# 9_-_STM32F407_Controller.net
KiCad netlist of a schematic drawn in Altium Designer
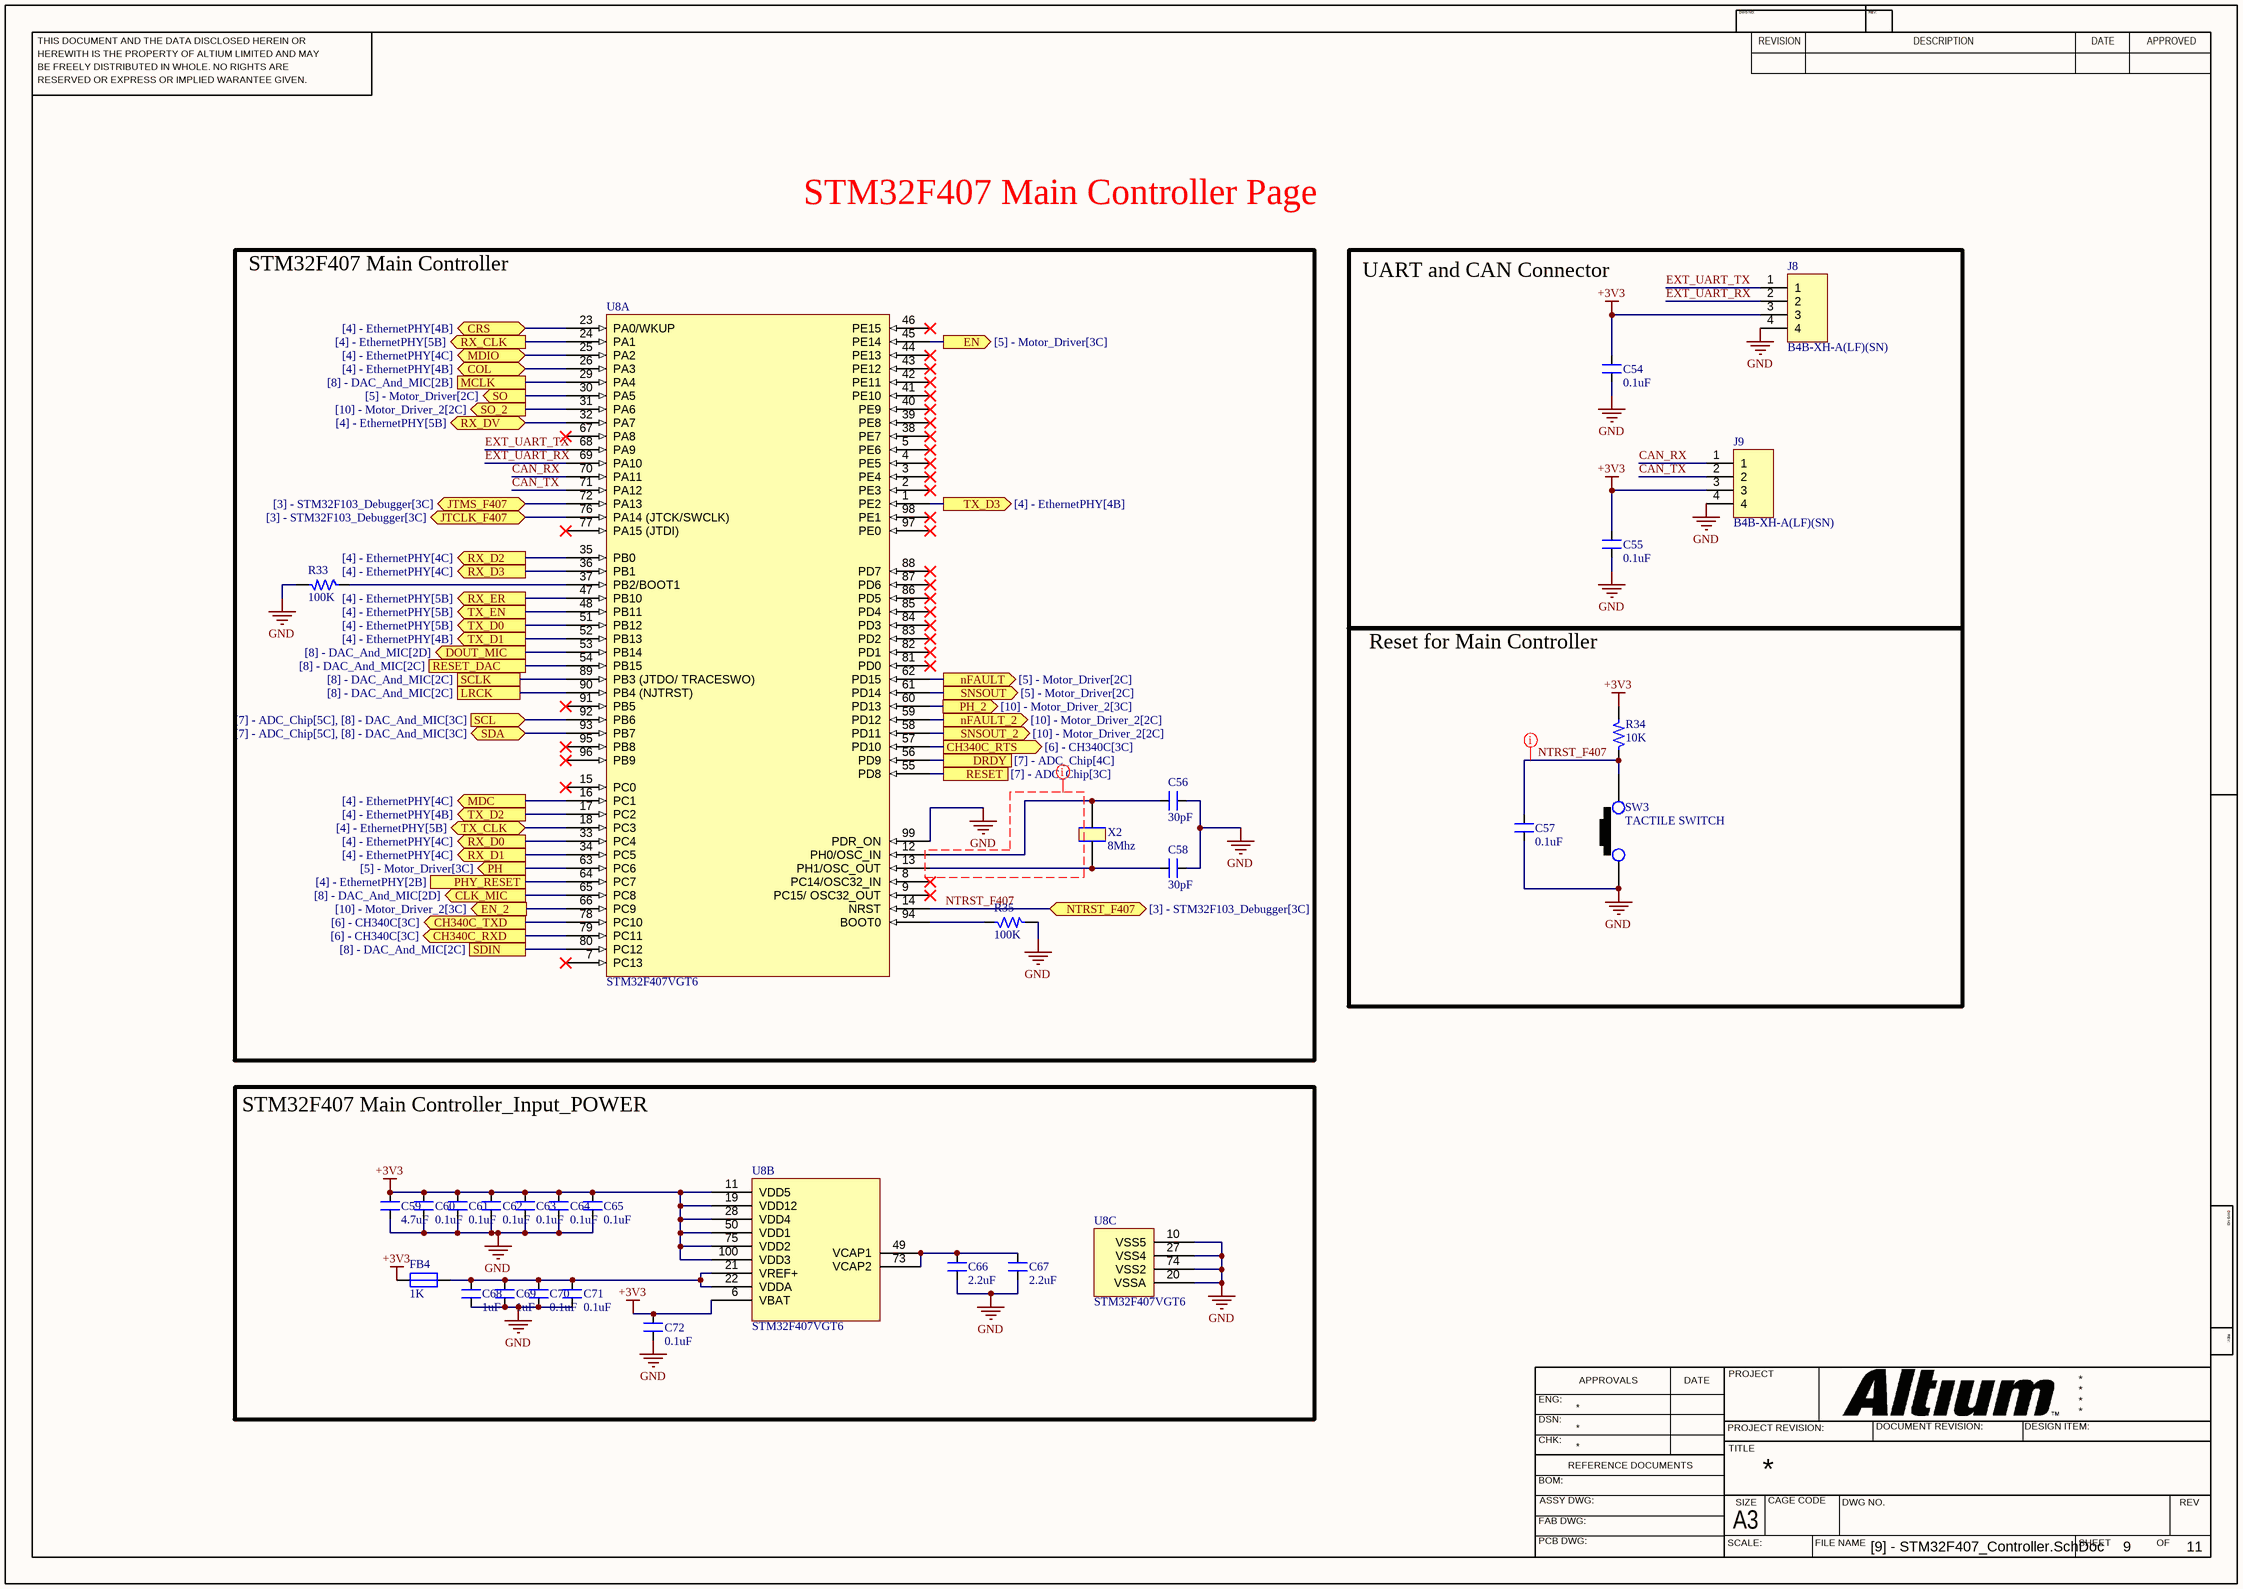
[diagram p0: [9] - STM32F407_Controller.SchDoc]

(export (version "E")
  (design (tool "Eeschema 10.0.6"))
  (components
    (comp (ref "C54")
      (value "0.1uF")
      (footprint "CAP_0805")
      (description "0.1µF ±5% 50V Ceramic Capacitor X7R 0805 (2012 Metric)")
      (fields
        (field (name "MANUFACTURER") "AVX Corporation")
        (field (name "MANUFACTURER PART NUMBER") "08055C104JAT4A")
      )
      (libsource (lib "ESTEEMPCBLIB") (part "CAP_0.1uF-50V-5%-0805"))
    )
    (comp (ref "C55")
      (value "0.1uF")
      (footprint "CAP_0805")
      (description "0.1µF ±5% 50V Ceramic Capacitor X7R 0805 (2012 Metric)")
      (fields
        (field (name "MANUFACTURER") "AVX Corporation")
        (field (name "MANUFACTURER PART NUMBER") "08055C104JAT4A")
      )
      (libsource (lib "ESTEEMPCBLIB") (part "CAP_0.1uF-50V-5%-0805"))
    )
    (comp (ref "C56")
      (value "30pF")
      (footprint "CAP_0805")
      (description "±10% 50V Ceramic Capacitor C0G, NP0 0805 (2012 Metric)")
      (fields
        (field (name "MANUFACTURER PART NUMBER") "C0805C300K5GAC7800")
        (field (name "MANUFACTURER") "KEMET")
      )
      (libsource (lib "ESTEEMPCBLIB") (part "CAP_30pF-50V-10%-0805"))
    )
    (comp (ref "C57")
      (value "0.1uF")
      (footprint "CAP_0805")
      (description "0.1µF ±5% 50V Ceramic Capacitor X7R 0805 (2012 Metric)")
      (fields
        (field (name "MANUFACTURER") "AVX Corporation")
        (field (name "MANUFACTURER PART NUMBER") "08055C104JAT4A")
      )
      (libsource (lib "ESTEEMPCBLIB") (part "CAP_0.1uF-50V-5%-0805"))
    )
    (comp (ref "C58")
      (value "30pF")
      (footprint "CAP_0805")
      (description "±10% 50V Ceramic Capacitor C0G, NP0 0805 (2012 Metric)")
      (fields
        (field (name "MANUFACTURER PART NUMBER") "C0805C300K5GAC7800")
        (field (name "MANUFACTURER") "KEMET")
      )
      (libsource (lib "ESTEEMPCBLIB") (part "CAP_30pF-50V-10%-0805"))
    )
    (comp (ref "C59")
      (value "4.7uF")
      (footprint "CAP_0805")
      (description "4.7µF ±10% 50V Ceramic Capacitor X5R 0805 (2012 Metric)")
      (fields
        (field (name "MANUFACTURER") "Yageo")
        (field (name "MANUFACTURER PART NUMBER") "GRM21BR61H475KE51L")
      )
      (libsource (lib "ESTEEMPCBLIB") (part "CAP_4.7uF-50V-10%-0805"))
    )
    (comp (ref "C60")
      (value "0.1uF")
      (footprint "CAP_0805")
      (description "0.1µF ±5% 50V Ceramic Capacitor X7R 0805 (2012 Metric)")
      (fields
        (field (name "MANUFACTURER") "AVX Corporation")
        (field (name "MANUFACTURER PART NUMBER") "08055C104JAT4A")
      )
      (libsource (lib "ESTEEMPCBLIB") (part "CAP_0.1uF-50V-5%-0805"))
    )
    (comp (ref "C61")
      (value "0.1uF")
      (footprint "CAP_0805")
      (description "0.1µF ±5% 50V Ceramic Capacitor X7R 0805 (2012 Metric)")
      (fields
        (field (name "MANUFACTURER") "AVX Corporation")
        (field (name "MANUFACTURER PART NUMBER") "08055C104JAT4A")
      )
      (libsource (lib "ESTEEMPCBLIB") (part "CAP_0.1uF-50V-5%-0805"))
    )
    (comp (ref "C62")
      (value "0.1uF")
      (footprint "CAP_0805")
      (description "0.1µF ±5% 50V Ceramic Capacitor X7R 0805 (2012 Metric)")
      (fields
        (field (name "MANUFACTURER") "AVX Corporation")
        (field (name "MANUFACTURER PART NUMBER") "08055C104JAT4A")
      )
      (libsource (lib "ESTEEMPCBLIB") (part "CAP_0.1uF-50V-5%-0805"))
    )
    (comp (ref "C63")
      (value "0.1uF")
      (footprint "CAP_0805")
      (description "0.1µF ±5% 50V Ceramic Capacitor X7R 0805 (2012 Metric)")
      (fields
        (field (name "MANUFACTURER") "AVX Corporation")
        (field (name "MANUFACTURER PART NUMBER") "08055C104JAT4A")
      )
      (libsource (lib "ESTEEMPCBLIB") (part "CAP_0.1uF-50V-5%-0805"))
    )
    (comp (ref "C64")
      (value "0.1uF")
      (footprint "CAP_0805")
      (description "0.1µF ±5% 50V Ceramic Capacitor X7R 0805 (2012 Metric)")
      (fields
        (field (name "MANUFACTURER") "AVX Corporation")
        (field (name "MANUFACTURER PART NUMBER") "08055C104JAT4A")
      )
      (libsource (lib "ESTEEMPCBLIB") (part "CAP_0.1uF-50V-5%-0805"))
    )
    (comp (ref "C65")
      (value "0.1uF")
      (footprint "CAP_0805")
      (description "0.1µF ±5% 50V Ceramic Capacitor X7R 0805 (2012 Metric)")
      (fields
        (field (name "MANUFACTURER") "AVX Corporation")
        (field (name "MANUFACTURER PART NUMBER") "08055C104JAT4A")
      )
      (libsource (lib "ESTEEMPCBLIB") (part "CAP_0.1uF-50V-5%-0805"))
    )
    (comp (ref "C66")
      (value "2.2uF")
      (footprint "CAP_0805")
      (description "2.2µF ±10% 25V Ceramic Capacitor X7R 0805 (2012 Metric)")
      (fields
        (field (name "MANUFACTURER") "KEMET")
        (field (name "MANUFACTURER PART NUMBER") "CL21B225KAFNFNE")
      )
      (libsource (lib "ESTEEMPCBLIB") (part "CAP_2.2uF-25V-10%-0805"))
    )
    (comp (ref "C67")
      (value "2.2uF")
      (footprint "CAP_0805")
      (description "2.2µF ±10% 25V Ceramic Capacitor X7R 0805 (2012 Metric)")
      (fields
        (field (name "MANUFACTURER") "KEMET")
        (field (name "MANUFACTURER PART NUMBER") "CL21B225KAFNFNE")
      )
      (libsource (lib "ESTEEMPCBLIB") (part "CAP_2.2uF-25V-10%-0805"))
    )
    (comp (ref "C68")
      (value "1uF")
      (footprint "CAP_0805")
      (description "1µF ±5% 50V Ceramic Capacitor X7R 0805 (2012 Metric)")
      (fields
        (field (name "MANUFACTURER") "Samsung")
        (field (name "MANUFACTURER PART NUMBER") "CC0805JKX7R9BB105")
      )
      (libsource (lib "ESTEEMPCBLIB") (part "CAP_1uF-50V-5%-0805"))
    )
    (comp (ref "C69")
      (value "1uF")
      (footprint "CAP_0805")
      (description "1µF ±5% 50V Ceramic Capacitor X7R 0805 (2012 Metric)")
      (fields
        (field (name "MANUFACTURER") "Samsung")
        (field (name "MANUFACTURER PART NUMBER") "CC0805JKX7R9BB105")
      )
      (libsource (lib "ESTEEMPCBLIB") (part "CAP_1uF-50V-5%-0805"))
    )
    (comp (ref "C70")
      (value "0.1uF")
      (footprint "CAP_0805")
      (description "0.1µF ±5% 50V Ceramic Capacitor X7R 0805 (2012 Metric)")
      (fields
        (field (name "MANUFACTURER") "AVX Corporation")
        (field (name "MANUFACTURER PART NUMBER") "08055C104JAT4A")
      )
      (libsource (lib "ESTEEMPCBLIB") (part "CAP_0.1uF-50V-5%-0805"))
    )
    (comp (ref "C71")
      (value "0.1uF")
      (footprint "CAP_0805")
      (description "0.1µF ±5% 50V Ceramic Capacitor X7R 0805 (2012 Metric)")
      (fields
        (field (name "MANUFACTURER") "AVX Corporation")
        (field (name "MANUFACTURER PART NUMBER") "08055C104JAT4A")
      )
      (libsource (lib "ESTEEMPCBLIB") (part "CAP_0.1uF-50V-5%-0805"))
    )
    (comp (ref "C72")
      (value "0.1uF")
      (footprint "CAP_0805")
      (description "0.1µF ±5% 50V Ceramic Capacitor X7R 0805 (2012 Metric)")
      (fields
        (field (name "MANUFACTURER") "AVX Corporation")
        (field (name "MANUFACTURER PART NUMBER") "08055C104JAT4A")
      )
      (libsource (lib "ESTEEMPCBLIB") (part "CAP_0.1uF-50V-5%-0805"))
    )
    (comp (ref "FB4")
      (value "1K")
      (footprint "IND_0805")
      (description "1 kOhms @ 100MHz 1 Power Line Ferrite Bead 0805 (2012 Metric) 1.6A")
      (fields
        (field (name "MANUFACTURER") "Laird")
        (field (name "MANUFACTURER PART NUMBER") "BLM21SP102SH1D")
      )
      (libsource (lib "ESTEEMPCBLIB") (part "FB_1K-100MHZ-1.6A-0805"))
    )
    (comp (ref "J8")
      (value "B4B-XH-A(LF)(SN)")
      (footprint "CON4_100_B4B-XH-A_TH_ST")
      (description "4 Pins, 1 Row 2.54mm Pitch, straight Connector, male")
      (fields (field (name "MANUFACTURER") "Wurth Electronics") (field (name "MATING PART NUMBER") "XHP-4"))
      (libsource (lib "ESTEEMPCBLIB") (part "CON-PLG_4X1-100-ST-TH"))
    )
    (comp (ref "J9")
      (value "B4B-XH-A(LF)(SN)")
      (footprint "CON4_100_B4B-XH-A_TH_ST")
      (description "4 Pins, 1 Row 2.54mm Pitch, straight Connector, male")
      (fields (field (name "MANUFACTURER") "Wurth Electronics") (field (name "MATING PART NUMBER") "XHP-4"))
      (libsource (lib "ESTEEMPCBLIB") (part "CON-PLG_4X1-100-ST-TH"))
    )
    (comp (ref "R33")
      (value "100K")
      (footprint "RES_0805")
      (description "100 kOhms ±1% 0.125W, 1/8W Chip Resistor 0805 (2012 Metric) Automotive AEC-Q200 Thick Film")
      (fields (field (name "MANUFACTURER") "Walsin") (field (name "MANUFACTURER PART NUMBER") "WR08X1003FTL"))
      (libsource (lib "ESTEEMPCBLIB") (part "RES_100K-0.125W-1%-0805"))
    )
    (comp (ref "R34")
      (value "10K")
      (footprint "RES_0805")
      (description "10 kOhms ±1% 0.125W, 1/8W Chip Resistor 0805 (2012 Metric) Automotive AEC-Q200 Thick Film")
      (fields (field (name "MANUFACTURER") "CTS") (field (name "MANUFACTURER PART NUMBER") "WR08X1002FTL"))
      (libsource (lib "ESTEEMPCBLIB") (part "RES_10K-0.125W-1%-0805"))
    )
    (comp (ref "R35")
      (value "100K")
      (footprint "RES_0805")
      (description "100 kOhms ±1% 0.125W, 1/8W Chip Resistor 0805 (2012 Metric) Automotive AEC-Q200 Thick Film")
      (fields (field (name "MANUFACTURER") "Walsin") (field (name "MANUFACTURER PART NUMBER") "WR08X1003FTL"))
      (libsource (lib "ESTEEMPCBLIB") (part "RES_100K-0.125W-1%-0805"))
    )
    (comp (ref "SW3")
      (value "TACTILE SWITCH")
      (footprint "SW_342_SMD")
      (description "Tactile Switch SPST-NO Top Actuated Surface Mount")
      (fields
        (field (name "MANUFACTURER") "ITT C&K")
        (field (name "MANUFACTURER PART NUMBER") "RS-282G05A3-SMRT")
      )
      (libsource (lib "ESTEEMPCBLIB") (part "SW1_RS-282G05A3-SMRT-SMD"))
    )
    (comp (ref "U8")
      (value "STM32F407VGT6")
      (footprint "QFN100_19.6_669_58X10_SMD")
      (description "ARM® Cortex®-M4 STM32F4 Microcontroller IC 32-Bit 168MHz 1MB (1M x 8) FLASH 100-LQFP (14x14)")
      (fields (field (name "MANUFACTURER") "STMicroelectronics"))
      (libsource (lib "ESTEEMPCBLIB") (part "IC_STM32F407VGT6"))
    )
    (comp (ref "X2")
      (value "8Mhz")
      (footprint "XTAL_314_240X47_SMD")
      (description "8MHz ±30ppm Crystal 32pF 60 Ohms HC-49/US")
      (fields
        (field (name "MANUFACTURER") "Fox Electronics")
        (field (name "MANUFACTURER PART NUMBER") "ECS-80-32-5PX-TR")
      )
      (libsource (lib "ESTEEMPCBLIB") (part "XTAL_8MHZ-ECS-80-32-5PX-SMD"))
    )
  )
  (nets
    (net (code "1") (name "+3V3") (class "Default")
      (node (ref "C54") (pin "2") (pinfunction "2_2") (pintype "passive"))
      (node (ref "C55") (pin "2") (pinfunction "2_2") (pintype "passive"))
      (node (ref "C59") (pin "2") (pinfunction "2_2") (pintype "passive"))
      (node (ref "C60") (pin "2") (pinfunction "2_2") (pintype "passive"))
      (node (ref "C61") (pin "2") (pinfunction "2_2") (pintype "passive"))
      (node (ref "C62") (pin "2") (pinfunction "2_2") (pintype "passive"))
      (node (ref "C63") (pin "2") (pinfunction "2_2") (pintype "passive"))
      (node (ref "C64") (pin "2") (pinfunction "2_2") (pintype "passive"))
      (node (ref "C65") (pin "2") (pinfunction "2_2") (pintype "passive"))
      (node (ref "C72") (pin "2") (pinfunction "2_2") (pintype "passive"))
      (node (ref "FB4") (pin "1") (pinfunction "1_1") (pintype "passive"))
      (node (ref "J8") (pin "3") (pinfunction "3_3") (pintype "passive"))
      (node (ref "J9") (pin "3") (pinfunction "3_3") (pintype "passive"))
      (node (ref "R34") (pin "2") (pinfunction "2_2") (pintype "passive"))
      (node (ref "U8") (pin "100") (pinfunction "VDD3_100") (pintype "passive"))
      (node (ref "U8") (pin "11") (pinfunction "VDD5_11") (pintype "passive"))
      (node (ref "U8") (pin "19") (pinfunction "VDD12_19") (pintype "passive"))
      (node (ref "U8") (pin "28") (pinfunction "VDD4_28") (pintype "passive"))
      (node (ref "U8") (pin "50") (pinfunction "VDD1_50") (pintype "passive"))
      (node (ref "U8") (pin "6") (pinfunction "VBAT_6") (pintype "passive"))
      (node (ref "U8") (pin "75") (pinfunction "VDD2_75") (pintype "passive"))
    )
    (net (code "2") (name "/CAN_RX") (class "Default")
      (node (ref "J9") (pin "1") (pinfunction "1_1") (pintype "passive"))
      (node (ref "U8") (pin "70") (pinfunction "PA11_70") (pintype "input"))
    )
    (net (code "3") (name "/CAN_TX") (class "Default")
      (node (ref "J9") (pin "2") (pinfunction "2_2") (pintype "passive"))
      (node (ref "U8") (pin "71") (pinfunction "PA12_71") (pintype "input"))
    )
    (net (code "4") (name "/CH340C_RTS") (class "Default")
      (node (ref "U8") (pin "57") (pinfunction "PD10_57") (pintype "input"))
    )
    (net (code "5") (name "/CH340C_RXD") (class "Default")
      (node (ref "U8") (pin "79") (pinfunction "PC11_79") (pintype "input"))
    )
    (net (code "6") (name "/CH340C_TXD") (class "Default")
      (node (ref "U8") (pin "78") (pinfunction "PC10_78") (pintype "input"))
    )
    (net (code "7") (name "/CLK_MIC") (class "Default")
      (node (ref "U8") (pin "65") (pinfunction "PC8_65") (pintype "input"))
    )
    (net (code "8") (name "/COL") (class "Default")
      (node (ref "U8") (pin "26") (pinfunction "PA3_26") (pintype "input"))
    )
    (net (code "9") (name "/CRS") (class "Default")
      (node (ref "U8") (pin "23") (pinfunction "PA0/WKUP_23") (pintype "input"))
    )
    (net (code "10") (name "/DOUT_MIC") (class "Default")
      (node (ref "U8") (pin "53") (pinfunction "PB14_53") (pintype "input"))
    )
    (net (code "11") (name "/DRDY") (class "Default")
      (node (ref "U8") (pin "56") (pinfunction "PD9_56") (pintype "input"))
    )
    (net (code "12") (name "/EN") (class "Default")
      (node (ref "U8") (pin "45") (pinfunction "PE14_45") (pintype "input"))
    )
    (net (code "13") (name "/EN_2") (class "Default")
      (node (ref "U8") (pin "66") (pinfunction "PC9_66") (pintype "input"))
    )
    (net (code "14") (name "/EXT_UART_RX") (class "Default")
      (node (ref "J8") (pin "2") (pinfunction "2_2") (pintype "passive"))
      (node (ref "U8") (pin "69") (pinfunction "PA10_69") (pintype "input"))
    )
    (net (code "15") (name "/EXT_UART_TX") (class "Default")
      (node (ref "J8") (pin "1") (pinfunction "1_1") (pintype "passive"))
      (node (ref "U8") (pin "68") (pinfunction "PA9_68") (pintype "input"))
    )
    (net (code "16") (name "/JTCLK_F407") (class "Default")
      (node (ref "U8") (pin "76") (pinfunction "PA14_(JTCK/SWCLK)_76") (pintype "input"))
    )
    (net (code "17") (name "/JTMS_F407") (class "Default")
      (node (ref "U8") (pin "72") (pinfunction "PA13_72") (pintype "input"))
    )
    (net (code "18") (name "/LRCK") (class "Default")
      (node (ref "U8") (pin "90") (pinfunction "PB4_(NJTRST)_90") (pintype "input"))
    )
    (net (code "19") (name "/MCLK") (class "Default")
      (node (ref "U8") (pin "29") (pinfunction "PA4_29") (pintype "input"))
    )
    (net (code "20") (name "/MDC") (class "Default")
      (node (ref "U8") (pin "16") (pinfunction "PC1_16") (pintype "input"))
    )
    (net (code "21") (name "/MDIO") (class "Default")
      (node (ref "U8") (pin "25") (pinfunction "PA2_25") (pintype "input"))
    )
    (net (code "22") (name "/NTRST_F407") (class "Default")
      (node (ref "C57") (pin "2") (pinfunction "2_2") (pintype "passive"))
      (node (ref "R34") (pin "1") (pinfunction "1_1") (pintype "passive"))
      (node (ref "SW3") (pin "2") (pinfunction "2_2") (pintype "passive"))
      (node (ref "U8") (pin "14") (pinfunction "NRST_14") (pintype "input"))
    )
    (net (code "23") (name "/PH") (class "Default")
      (node (ref "U8") (pin "63") (pinfunction "PC6_63") (pintype "input"))
    )
    (net (code "24") (name "/PHY_RESET") (class "Default")
      (node (ref "U8") (pin "64") (pinfunction "PC7_64") (pintype "input"))
    )
    (net (code "25") (name "/PH_2") (class "Default")
      (node (ref "U8") (pin "60") (pinfunction "PD13_60") (pintype "input"))
    )
    (net (code "26") (name "/RESET") (class "Default")
      (node (ref "U8") (pin "55") (pinfunction "PD8_55") (pintype "input"))
    )
    (net (code "27") (name "/RESET_DAC") (class "Default")
      (node (ref "U8") (pin "54") (pinfunction "PB15_54") (pintype "input"))
    )
    (net (code "28") (name "/RX_CLK") (class "Default")
      (node (ref "U8") (pin "24") (pinfunction "PA1_24") (pintype "input"))
    )
    (net (code "29") (name "/RX_D0") (class "Default")
      (node (ref "U8") (pin "33") (pinfunction "PC4_33") (pintype "input"))
    )
    (net (code "30") (name "/RX_D1") (class "Default")
      (node (ref "U8") (pin "34") (pinfunction "PC5_34") (pintype "input"))
    )
    (net (code "31") (name "/RX_D2") (class "Default")
      (node (ref "U8") (pin "35") (pinfunction "PB0_35") (pintype "input"))
    )
    (net (code "32") (name "/RX_D3") (class "Default")
      (node (ref "U8") (pin "36") (pinfunction "PB1_36") (pintype "input"))
    )
    (net (code "33") (name "/RX_DV") (class "Default")
      (node (ref "U8") (pin "32") (pinfunction "PA7_32") (pintype "input"))
    )
    (net (code "34") (name "/RX_ER") (class "Default")
      (node (ref "U8") (pin "47") (pinfunction "PB10_47") (pintype "input"))
    )
    (net (code "35") (name "/SCL") (class "Default")
      (node (ref "U8") (pin "92") (pinfunction "PB6_92") (pintype "input"))
    )
    (net (code "36") (name "/SCLK") (class "Default")
      (node (ref "U8") (pin "89") (pinfunction "PB3_(JTDO/_TRACESWO)_89") (pintype "input"))
    )
    (net (code "37") (name "/SDA") (class "Default")
      (node (ref "U8") (pin "93") (pinfunction "PB7_93") (pintype "input"))
    )
    (net (code "38") (name "/SDIN") (class "Default")
      (node (ref "U8") (pin "80") (pinfunction "PC12_80") (pintype "input"))
    )
    (net (code "39") (name "/SNSOUT") (class "Default")
      (node (ref "U8") (pin "61") (pinfunction "PD14_61") (pintype "input"))
    )
    (net (code "40") (name "/SNSOUT_2") (class "Default")
      (node (ref "U8") (pin "58") (pinfunction "PD11_58") (pintype "input"))
    )
    (net (code "41") (name "/SO") (class "Default")
      (node (ref "U8") (pin "30") (pinfunction "PA5_30") (pintype "input"))
    )
    (net (code "42") (name "/SO_2") (class "Default")
      (node (ref "U8") (pin "31") (pinfunction "PA6_31") (pintype "input"))
    )
    (net (code "43") (name "/TX_CLK") (class "Default")
      (node (ref "U8") (pin "18") (pinfunction "PC3_18") (pintype "input"))
    )
    (net (code "44") (name "/TX_D0") (class "Default")
      (node (ref "U8") (pin "51") (pinfunction "PB12_51") (pintype "input"))
    )
    (net (code "45") (name "/TX_D1") (class "Default")
      (node (ref "U8") (pin "52") (pinfunction "PB13_52") (pintype "input"))
    )
    (net (code "46") (name "/TX_D2") (class "Default")
      (node (ref "U8") (pin "17") (pinfunction "PC2_17") (pintype "input"))
    )
    (net (code "47") (name "/TX_D3") (class "Default")
      (node (ref "U8") (pin "1") (pinfunction "PE2_1") (pintype "input"))
    )
    (net (code "48") (name "/TX_EN") (class "Default")
      (node (ref "U8") (pin "48") (pinfunction "PB11_48") (pintype "input"))
    )
    (net (code "49") (name "/nFAULT") (class "Default")
      (node (ref "U8") (pin "62") (pinfunction "PD15_62") (pintype "input"))
    )
    (net (code "50") (name "/nFAULT_2") (class "Default")
      (node (ref "U8") (pin "59") (pinfunction "PD12_59") (pintype "input"))
    )
    (net (code "51") (name "GND") (class "Default")
      (node (ref "C54") (pin "1") (pinfunction "1_1") (pintype "passive"))
      (node (ref "C55") (pin "1") (pinfunction "1_1") (pintype "passive"))
      (node (ref "C56") (pin "2") (pinfunction "2_2") (pintype "passive"))
      (node (ref "C57") (pin "1") (pinfunction "1_1") (pintype "passive"))
      (node (ref "C58") (pin "2") (pinfunction "2_2") (pintype "passive"))
      (node (ref "C59") (pin "1") (pinfunction "1_1") (pintype "passive"))
      (node (ref "C60") (pin "1") (pinfunction "1_1") (pintype "passive"))
      (node (ref "C61") (pin "1") (pinfunction "1_1") (pintype "passive"))
      (node (ref "C62") (pin "1") (pinfunction "1_1") (pintype "passive"))
      (node (ref "C63") (pin "1") (pinfunction "1_1") (pintype "passive"))
      (node (ref "C64") (pin "1") (pinfunction "1_1") (pintype "passive"))
      (node (ref "C65") (pin "1") (pinfunction "1_1") (pintype "passive"))
      (node (ref "C66") (pin "1") (pinfunction "1_1") (pintype "passive"))
      (node (ref "C67") (pin "1") (pinfunction "1_1") (pintype "passive"))
      (node (ref "C68") (pin "1") (pinfunction "1_1") (pintype "passive"))
      (node (ref "C69") (pin "1") (pinfunction "1_1") (pintype "passive"))
      (node (ref "C70") (pin "1") (pinfunction "1_1") (pintype "passive"))
      (node (ref "C71") (pin "1") (pinfunction "1_1") (pintype "passive"))
      (node (ref "C72") (pin "1") (pinfunction "1_1") (pintype "passive"))
      (node (ref "J8") (pin "4") (pinfunction "4_4") (pintype "passive"))
      (node (ref "J9") (pin "4") (pinfunction "4_4") (pintype "passive"))
      (node (ref "R33") (pin "2") (pinfunction "2_2") (pintype "passive"))
      (node (ref "R35") (pin "2") (pinfunction "2_2") (pintype "passive"))
      (node (ref "SW3") (pin "1") (pinfunction "1_1") (pintype "passive"))
      (node (ref "U8") (pin "10") (pinfunction "VSS5_10") (pintype "passive"))
      (node (ref "U8") (pin "20") (pinfunction "VSSA_20") (pintype "passive"))
      (node (ref "U8") (pin "27") (pinfunction "VSS4_27") (pintype "passive"))
      (node (ref "U8") (pin "74") (pinfunction "VSS2_74") (pintype "passive"))
      (node (ref "U8") (pin "99") (pinfunction "PDR_ON_99") (pintype "input"))
    )
    (net (code "52") (name "Net-(U8A-BOOT0)") (class "Default")
      (node (ref "R35") (pin "1") (pinfunction "1_1") (pintype "passive"))
      (node (ref "U8") (pin "94") (pinfunction "BOOT0_94") (pintype "input"))
    )
    (net (code "53") (name "Net-(U8A-PB2{slash}BOOT1)") (class "Default")
      (node (ref "R33") (pin "1") (pinfunction "1_1") (pintype "passive"))
      (node (ref "U8") (pin "37") (pinfunction "PB2/BOOT1_37") (pintype "input"))
    )
    (net (code "54") (name "Net-(U8A-PH0{slash}OSC_IN)") (class "Default")
      (node (ref "C56") (pin "1") (pinfunction "1_1") (pintype "passive"))
      (node (ref "U8") (pin "12") (pinfunction "PH0/OSC_IN_12") (pintype "input"))
      (node (ref "X2") (pin "2") (pinfunction "2_2") (pintype "passive"))
    )
    (net (code "55") (name "Net-(U8A-PH1{slash}OSC_OUT)") (class "Default")
      (node (ref "C58") (pin "1") (pinfunction "1_1") (pintype "passive"))
      (node (ref "U8") (pin "13") (pinfunction "PH1/OSC_OUT_13") (pintype "input"))
      (node (ref "X2") (pin "1") (pinfunction "1_1") (pintype "passive"))
    )
    (net (code "56") (name "Net-(U8B-VCAP1)") (class "Default")
      (node (ref "C66") (pin "2") (pinfunction "2_2") (pintype "passive"))
      (node (ref "C67") (pin "2") (pinfunction "2_2") (pintype "passive"))
      (node (ref "U8") (pin "49") (pinfunction "VCAP1_49") (pintype "passive"))
      (node (ref "U8") (pin "73") (pinfunction "VCAP2_73") (pintype "passive"))
    )
    (net (code "57") (name "Net-(U8B-VDDA)") (class "Default")
      (node (ref "C68") (pin "2") (pinfunction "2_2") (pintype "passive"))
      (node (ref "C69") (pin "2") (pinfunction "2_2") (pintype "passive"))
      (node (ref "C70") (pin "2") (pinfunction "2_2") (pintype "passive"))
      (node (ref "C71") (pin "2") (pinfunction "2_2") (pintype "passive"))
      (node (ref "FB4") (pin "2") (pinfunction "2_2") (pintype "passive"))
      (node (ref "U8") (pin "21") (pinfunction "VREF+_21") (pintype "passive"))
      (node (ref "U8") (pin "22") (pinfunction "VDDA_22") (pintype "passive"))
    )
    (net (code "58") (name "unconnected-(U8A-PA8-Pad67)") (class "Default")
      (node (ref "U8") (pin "67") (pinfunction "PA8_67") (pintype "input+no_connect"))
    )
    (net (code "59") (name "unconnected-(U8A-PA15_(JTDI)-Pad77)") (class "Default")
      (node (ref "U8") (pin "77") (pinfunction "PA15_(JTDI)_77") (pintype "input+no_connect"))
    )
    (net (code "60") (name "unconnected-(U8A-PB5-Pad91)") (class "Default")
      (node (ref "U8") (pin "91") (pinfunction "PB5_91") (pintype "input+no_connect"))
    )
    (net (code "61") (name "unconnected-(U8A-PB8-Pad95)") (class "Default")
      (node (ref "U8") (pin "95") (pinfunction "PB8_95") (pintype "input+no_connect"))
    )
    (net (code "62") (name "unconnected-(U8A-PB9-Pad96)") (class "Default")
      (node (ref "U8") (pin "96") (pinfunction "PB9_96") (pintype "input+no_connect"))
    )
    (net (code "63") (name "unconnected-(U8A-PC0-Pad15)") (class "Default")
      (node (ref "U8") (pin "15") (pinfunction "PC0_15") (pintype "input+no_connect"))
    )
    (net (code "64") (name "unconnected-(U8A-PC13-Pad7)") (class "Default")
      (node (ref "U8") (pin "7") (pinfunction "PC13_7") (pintype "input+no_connect"))
    )
    (net (code "65") (name "unconnected-(U8A-PC14{slash}OSC32_IN-Pad8)") (class "Default")
      (node (ref "U8") (pin "8") (pinfunction "PC14/OSC32_IN_8") (pintype "input+no_connect"))
    )
    (net (code "66") (name "unconnected-(U8A-PC15{slash}_OSC32_OUT-Pad9)") (class "Default")
      (node (ref "U8") (pin "9") (pinfunction "PC15/_OSC32_OUT_9") (pintype "input+no_connect"))
    )
    (net (code "67") (name "unconnected-(U8A-PD0-Pad81)") (class "Default")
      (node (ref "U8") (pin "81") (pinfunction "PD0_81") (pintype "input+no_connect"))
    )
    (net (code "68") (name "unconnected-(U8A-PD1-Pad82)") (class "Default")
      (node (ref "U8") (pin "82") (pinfunction "PD1_82") (pintype "input+no_connect"))
    )
    (net (code "69") (name "unconnected-(U8A-PD2-Pad83)") (class "Default")
      (node (ref "U8") (pin "83") (pinfunction "PD2_83") (pintype "input+no_connect"))
    )
    (net (code "70") (name "unconnected-(U8A-PD3-Pad84)") (class "Default")
      (node (ref "U8") (pin "84") (pinfunction "PD3_84") (pintype "input+no_connect"))
    )
    (net (code "71") (name "unconnected-(U8A-PD4-Pad85)") (class "Default")
      (node (ref "U8") (pin "85") (pinfunction "PD4_85") (pintype "input+no_connect"))
    )
    (net (code "72") (name "unconnected-(U8A-PD5-Pad86)") (class "Default")
      (node (ref "U8") (pin "86") (pinfunction "PD5_86") (pintype "input+no_connect"))
    )
    (net (code "73") (name "unconnected-(U8A-PD6-Pad87)") (class "Default")
      (node (ref "U8") (pin "87") (pinfunction "PD6_87") (pintype "input+no_connect"))
    )
    (net (code "74") (name "unconnected-(U8A-PD7-Pad88)") (class "Default")
      (node (ref "U8") (pin "88") (pinfunction "PD7_88") (pintype "input+no_connect"))
    )
    (net (code "75") (name "unconnected-(U8A-PE0-Pad97)") (class "Default")
      (node (ref "U8") (pin "97") (pinfunction "PE0_97") (pintype "input+no_connect"))
    )
    (net (code "76") (name "unconnected-(U8A-PE1-Pad98)") (class "Default")
      (node (ref "U8") (pin "98") (pinfunction "PE1_98") (pintype "input+no_connect"))
    )
    (net (code "77") (name "unconnected-(U8A-PE3-Pad2)") (class "Default")
      (node (ref "U8") (pin "2") (pinfunction "PE3_2") (pintype "input+no_connect"))
    )
    (net (code "78") (name "unconnected-(U8A-PE4-Pad3)") (class "Default")
      (node (ref "U8") (pin "3") (pinfunction "PE4_3") (pintype "input+no_connect"))
    )
    (net (code "79") (name "unconnected-(U8A-PE5-Pad4)") (class "Default")
      (node (ref "U8") (pin "4") (pinfunction "PE5_4") (pintype "input+no_connect"))
    )
    (net (code "80") (name "unconnected-(U8A-PE6-Pad5)") (class "Default")
      (node (ref "U8") (pin "5") (pinfunction "PE6_5") (pintype "input+no_connect"))
    )
    (net (code "81") (name "unconnected-(U8A-PE7-Pad38)") (class "Default")
      (node (ref "U8") (pin "38") (pinfunction "PE7_38") (pintype "input+no_connect"))
    )
    (net (code "82") (name "unconnected-(U8A-PE8-Pad39)") (class "Default")
      (node (ref "U8") (pin "39") (pinfunction "PE8_39") (pintype "input+no_connect"))
    )
    (net (code "83") (name "unconnected-(U8A-PE9-Pad40)") (class "Default")
      (node (ref "U8") (pin "40") (pinfunction "PE9_40") (pintype "input+no_connect"))
    )
    (net (code "84") (name "unconnected-(U8A-PE10-Pad41)") (class "Default")
      (node (ref "U8") (pin "41") (pinfunction "PE10_41") (pintype "input+no_connect"))
    )
    (net (code "85") (name "unconnected-(U8A-PE11-Pad42)") (class "Default")
      (node (ref "U8") (pin "42") (pinfunction "PE11_42") (pintype "input+no_connect"))
    )
    (net (code "86") (name "unconnected-(U8A-PE12-Pad43)") (class "Default")
      (node (ref "U8") (pin "43") (pinfunction "PE12_43") (pintype "input+no_connect"))
    )
    (net (code "87") (name "unconnected-(U8A-PE13-Pad44)") (class "Default")
      (node (ref "U8") (pin "44") (pinfunction "PE13_44") (pintype "input+no_connect"))
    )
    (net (code "88") (name "unconnected-(U8A-PE15-Pad46)") (class "Default")
      (node (ref "U8") (pin "46") (pinfunction "PE15_46") (pintype "input+no_connect"))
    )
  )
)
